# Y9A_4.net
KiCad netlist of a schematic drawn in Altium Designer
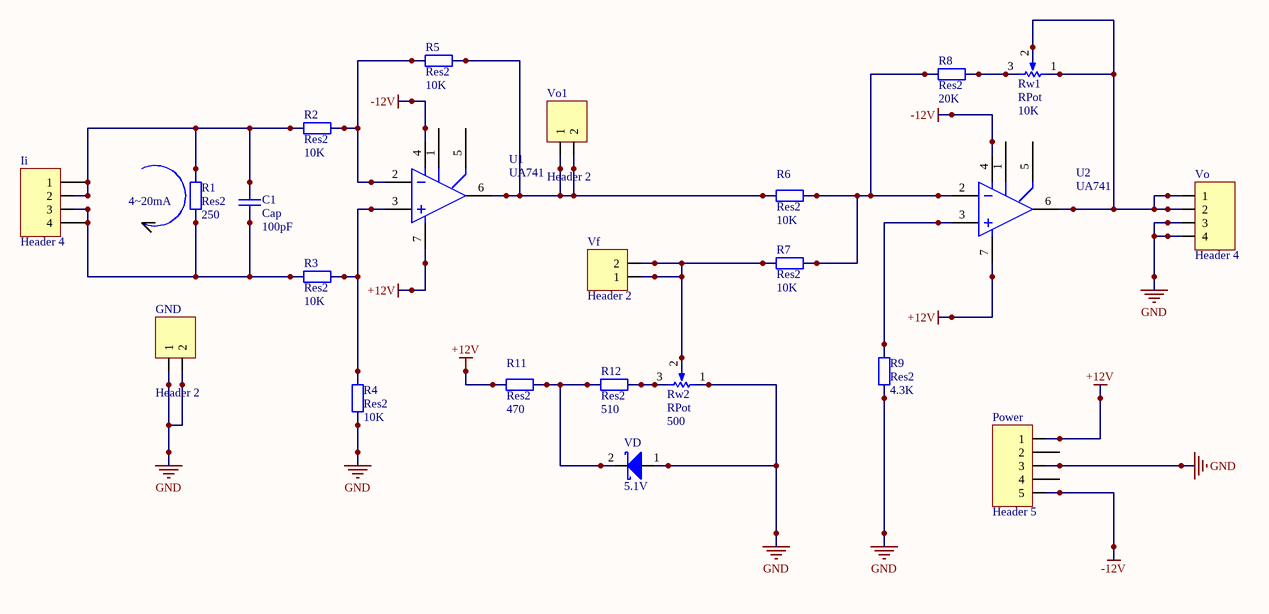
[diagram p0: Y9A_4.SchDoc]

(export (version "E")
  (design (tool "Eeschema 10.0.6"))
  (components
    (comp (ref "C1")
      (value "Cap")
      (footprint "RAD-0.2")
      (description "Capacitor")
      (fields (field (name "ALTIUM_VALUE") "100pF") (field (name "PUBLISHER") "Altium Limited"))
      (libsource (lib "Miscellaneous Devices") (part "Cap"))
    )
    (comp (ref "GND")
      (value "Header 2")
      (footprint "SIP-2")
      (description "Header, 2-Pin")
      (fields (field (name "PUBLISHER") "Altium Limited"))
      (libsource (lib "Miscellaneous Connectors") (part "Header 2"))
    )
    (comp (ref "Ii")
      (value "Header 4")
      (footprint "SIP-4")
      (description "Header, 4-Pin")
      (fields (field (name "PUBLISHER") "Altium Limited"))
      (libsource (lib "") (part "Header 4_1"))
    )
    (comp (ref "Power")
      (value "Header 5")
      (footprint "POWER PLUG5")
      (description "Header, 5-Pin")
      (fields (field (name "PUBLISHER") "Altium Limited"))
      (libsource (lib "Miscellaneous Connectors") (part "Header 5"))
    )
    (comp (ref "R1")
      (value "Res2")
      (footprint "AXIAL-0.4")
      (description "Resistor")
      (fields (field (name "ALTIUM_VALUE") "250") (field (name "PUBLISHER") "Altium Limited"))
      (libsource (lib "") (part "Res2_1"))
    )
    (comp (ref "R2")
      (value "Res2")
      (footprint "AXIAL-0.4")
      (description "Resistor")
      (fields (field (name "ALTIUM_VALUE") "10K") (field (name "PUBLISHER") "Altium Limited"))
      (libsource (lib "") (part "Res2_2"))
    )
    (comp (ref "R3")
      (value "Res2")
      (footprint "AXIAL-0.4")
      (description "Resistor")
      (fields (field (name "ALTIUM_VALUE") "10K") (field (name "PUBLISHER") "Altium Limited"))
      (libsource (lib "Miscellaneous Devices") (part "Res2"))
    )
    (comp (ref "R4")
      (value "Res2")
      (footprint "AXIAL-0.4")
      (description "Resistor")
      (fields (field (name "ALTIUM_VALUE") "10K") (field (name "PUBLISHER") "Altium Limited"))
      (libsource (lib "") (part "Res2_1"))
    )
    (comp (ref "R5")
      (value "Res2")
      (footprint "AXIAL-0.4")
      (description "Resistor")
      (fields (field (name "ALTIUM_VALUE") "10K") (field (name "PUBLISHER") "Altium Limited"))
      (libsource (lib "Miscellaneous Devices") (part "Res2"))
    )
    (comp (ref "R6")
      (value "Res2")
      (footprint "AXIAL-0.4")
      (description "Resistor")
      (fields (field (name "ALTIUM_VALUE") "10K") (field (name "PUBLISHER") "Altium Limited"))
      (libsource (lib "Miscellaneous Devices") (part "Res2"))
    )
    (comp (ref "R7")
      (value "Res2")
      (footprint "AXIAL-0.4")
      (description "Resistor")
      (fields (field (name "ALTIUM_VALUE") "10K") (field (name "PUBLISHER") "Altium Limited"))
      (libsource (lib "Miscellaneous Devices") (part "Res2"))
    )
    (comp (ref "R8")
      (value "Res2")
      (footprint "AXIAL-0.4")
      (description "Resistor")
      (fields (field (name "ALTIUM_VALUE") "20K") (field (name "PUBLISHER") "Altium Limited"))
      (libsource (lib "Miscellaneous Devices") (part "Res2"))
    )
    (comp (ref "R9")
      (value "Res2")
      (footprint "AXIAL-0.4")
      (description "Resistor")
      (fields (field (name "ALTIUM_VALUE") "4.3K") (field (name "PUBLISHER") "Altium Limited"))
      (libsource (lib "") (part "Res2_1"))
    )
    (comp (ref "R11")
      (value "Res2")
      (footprint "AXIAL-0.4")
      (description "Resistor")
      (fields (field (name "ALTIUM_VALUE") "470") (field (name "PUBLISHER") "Altium Limited"))
      (libsource (lib "Miscellaneous Devices") (part "Res2"))
    )
    (comp (ref "R12")
      (value "Res2")
      (footprint "AXIAL-0.4")
      (description "Resistor")
      (fields (field (name "ALTIUM_VALUE") "510") (field (name "PUBLISHER") "Altium Limited"))
      (libsource (lib "Miscellaneous Devices") (part "Res2"))
    )
    (comp (ref "Rw1")
      (value "RPot")
      (footprint "VR5")
      (description "Potentiometer")
      (fields (field (name "ALTIUM_VALUE") "10K") (field (name "PUBLISHER") "Altium Limited"))
      (libsource (lib "Miscellaneous Devices") (part "RPot"))
    )
    (comp (ref "Rw2")
      (value "RPot")
      (footprint "VR5")
      (description "Potentiometer")
      (fields (field (name "ALTIUM_VALUE") "500") (field (name "PUBLISHER") "Altium Limited"))
      (libsource (lib "Miscellaneous Devices") (part "RPot"))
    )
    (comp (ref "U1")
      (value "UA741")
      (footprint "DIP-8")
      (libsource (lib "Schematic Operational Amplifiers") (part "UA741"))
    )
    (comp (ref "U2")
      (value "UA741")
      (footprint "DIP-8")
      (libsource (lib "Schematic Operational Amplifiers") (part "UA741"))
    )
    (comp (ref "VD")
      (value "5.1V")
      (footprint "DIODE-0.4")
      (description "Schottky Diode")
      (fields (field (name "PUBLISHER") "Altium Limited"))
      (libsource (lib "Miscellaneous Devices") (part "D Schottky"))
    )
    (comp (ref "Vf")
      (value "Header 2")
      (footprint "SIP-2")
      (description "Header, 2-Pin")
      (fields (field (name "PUBLISHER") "Altium Limited"))
      (libsource (lib "") (part "Header 2_1"))
    )
    (comp (ref "Vo")
      (value "Header 4")
      (footprint "SIP-4")
      (description "Header, 4-Pin")
      (fields (field (name "PUBLISHER") "Altium Limited"))
      (libsource (lib "Miscellaneous Connectors") (part "Header 4"))
    )
    (comp (ref "Vo1")
      (value "Header 2")
      (footprint "SIP-2")
      (description "Header, 2-Pin")
      (fields (field (name "PUBLISHER") "Altium Limited"))
      (libsource (lib "Miscellaneous Connectors") (part "Header 2"))
    )
  )
  (nets
    (net (code "1") (name "+12V") (class "Default")
      (node (ref "Power") (pin "1") (pinfunction "1_1") (pintype "passive"))
      (node (ref "R11") (pin "1") (pinfunction "1_1") (pintype "passive"))
      (node (ref "U1") (pin "7") (pintype "passive"))
      (node (ref "U2") (pin "7") (pintype "passive"))
    )
    (net (code "2") (name "-12V") (class "Default")
      (node (ref "Power") (pin "5") (pinfunction "5_5") (pintype "passive"))
      (node (ref "U1") (pin "4") (pintype "passive"))
      (node (ref "U2") (pin "4") (pintype "passive"))
    )
    (net (code "3") (name "GND") (class "Default")
      (node (ref "GND") (pin "1") (pinfunction "1_1") (pintype "passive"))
      (node (ref "GND") (pin "2") (pinfunction "2_2") (pintype "passive"))
      (node (ref "Power") (pin "3") (pinfunction "3_3") (pintype "passive"))
      (node (ref "R4") (pin "1") (pinfunction "1_1") (pintype "passive"))
      (node (ref "R9") (pin "1") (pinfunction "1_1") (pintype "passive"))
      (node (ref "Rw2") (pin "1") (pinfunction "TOP_1") (pintype "passive"))
      (node (ref "VD") (pin "1") (pinfunction "1_1") (pintype "passive"))
      (node (ref "Vo") (pin "3") (pinfunction "3_3") (pintype "passive"))
      (node (ref "Vo") (pin "4") (pinfunction "4_4") (pintype "passive"))
    )
    (net (code "4") (name "Net-(C1-Pad1)") (class "Default")
      (node (ref "C1") (pin "1") (pinfunction "1_1") (pintype "passive"))
      (node (ref "Ii") (pin "3") (pinfunction "3_3") (pintype "passive"))
      (node (ref "Ii") (pin "4") (pinfunction "4_4") (pintype "passive"))
      (node (ref "R1") (pin "1") (pinfunction "1_1") (pintype "passive"))
      (node (ref "R3") (pin "1") (pinfunction "1_1") (pintype "passive"))
    )
    (net (code "5") (name "Net-(C1-Pad2)") (class "Default")
      (node (ref "C1") (pin "2") (pinfunction "2_2") (pintype "passive"))
      (node (ref "Ii") (pin "1") (pinfunction "1_1") (pintype "passive"))
      (node (ref "Ii") (pin "2") (pinfunction "2_2") (pintype "passive"))
      (node (ref "R1") (pin "2") (pinfunction "2_2") (pintype "passive"))
      (node (ref "R2") (pin "2") (pinfunction "2_2") (pintype "passive"))
    )
    (net (code "6") (name "Net-(R2-Pad1)") (class "Default")
      (node (ref "R2") (pin "1") (pinfunction "1_1") (pintype "passive"))
      (node (ref "R5") (pin "1") (pinfunction "1_1") (pintype "passive"))
      (node (ref "U1") (pin "2") (pintype "passive"))
    )
    (net (code "7") (name "Net-(R3-Pad2)") (class "Default")
      (node (ref "R3") (pin "2") (pinfunction "2_2") (pintype "passive"))
      (node (ref "R4") (pin "2") (pinfunction "2_2") (pintype "passive"))
      (node (ref "U1") (pin "3") (pintype "passive"))
    )
    (net (code "8") (name "Net-(R5-Pad2)") (class "Default")
      (node (ref "R5") (pin "2") (pinfunction "2_2") (pintype "passive"))
      (node (ref "R6") (pin "1") (pinfunction "1_1") (pintype "passive"))
      (node (ref "U1") (pin "6") (pintype "passive"))
      (node (ref "Vo1") (pin "1") (pinfunction "1_1") (pintype "passive"))
      (node (ref "Vo1") (pin "2") (pinfunction "2_2") (pintype "passive"))
    )
    (net (code "9") (name "Net-(R6-Pad2)") (class "Default")
      (node (ref "R6") (pin "2") (pinfunction "2_2") (pintype "passive"))
      (node (ref "R7") (pin "2") (pinfunction "2_2") (pintype "passive"))
      (node (ref "R8") (pin "1") (pinfunction "1_1") (pintype "passive"))
      (node (ref "U2") (pin "2") (pintype "passive"))
    )
    (net (code "10") (name "Net-(R9-Pad2)") (class "Default")
      (node (ref "R9") (pin "2") (pinfunction "2_2") (pintype "passive"))
      (node (ref "U2") (pin "3") (pintype "passive"))
    )
    (net (code "11") (name "Net-(R11-Pad2)") (class "Default")
      (node (ref "R11") (pin "2") (pinfunction "2_2") (pintype "passive"))
      (node (ref "R12") (pin "1") (pinfunction "1_1") (pintype "passive"))
      (node (ref "VD") (pin "2") (pinfunction "2_2") (pintype "passive"))
    )
    (net (code "12") (name "Net-(Rw1-BOT)") (class "Default")
      (node (ref "R8") (pin "2") (pinfunction "2_2") (pintype "passive"))
      (node (ref "Rw1") (pin "3") (pinfunction "BOT_3") (pintype "passive"))
    )
    (net (code "13") (name "Net-(Rw1-TAP)") (class "Default")
      (node (ref "Rw1") (pin "1") (pinfunction "TOP_1") (pintype "passive"))
      (node (ref "Rw1") (pin "2") (pinfunction "TAP_2") (pintype "passive"))
      (node (ref "U2") (pin "6") (pintype "passive"))
      (node (ref "Vo") (pin "1") (pinfunction "1_1") (pintype "passive"))
      (node (ref "Vo") (pin "2") (pinfunction "2_2") (pintype "passive"))
    )
    (net (code "14") (name "Net-(Rw2-BOT)") (class "Default")
      (node (ref "R12") (pin "2") (pinfunction "2_2") (pintype "passive"))
      (node (ref "Rw2") (pin "3") (pinfunction "BOT_3") (pintype "passive"))
    )
    (net (code "15") (name "Net-(Rw2-TAP)") (class "Default")
      (node (ref "R7") (pin "1") (pinfunction "1_1") (pintype "passive"))
      (node (ref "Rw2") (pin "2") (pinfunction "TAP_2") (pintype "passive"))
      (node (ref "Vf") (pin "1") (pinfunction "1_1") (pintype "passive"))
      (node (ref "Vf") (pin "2") (pinfunction "2_2") (pintype "passive"))
    )
    (net (code "16") (name "unconnected-(Power-Pad2)") (class "Default")
      (node (ref "Power") (pin "2") (pinfunction "2_2") (pintype "passive"))
    )
    (net (code "17") (name "unconnected-(Power-Pad4)") (class "Default")
      (node (ref "Power") (pin "4") (pinfunction "4_4") (pintype "passive"))
    )
    (net (code "18") (name "unconnected-(U1-Pad1)") (class "Default")
      (node (ref "U1") (pin "1") (pintype "passive"))
    )
    (net (code "19") (name "unconnected-(U1-Pad5)") (class "Default")
      (node (ref "U1") (pin "5") (pintype "passive"))
    )
    (net (code "20") (name "unconnected-(U2-Pad1)") (class "Default")
      (node (ref "U2") (pin "1") (pintype "passive"))
    )
    (net (code "21") (name "unconnected-(U2-Pad5)") (class "Default")
      (node (ref "U2") (pin "5") (pintype "passive"))
    )
  )
)
